# VOLTAGE_SOURCE.net
KiCad netlist of a schematic drawn in Altium Designer
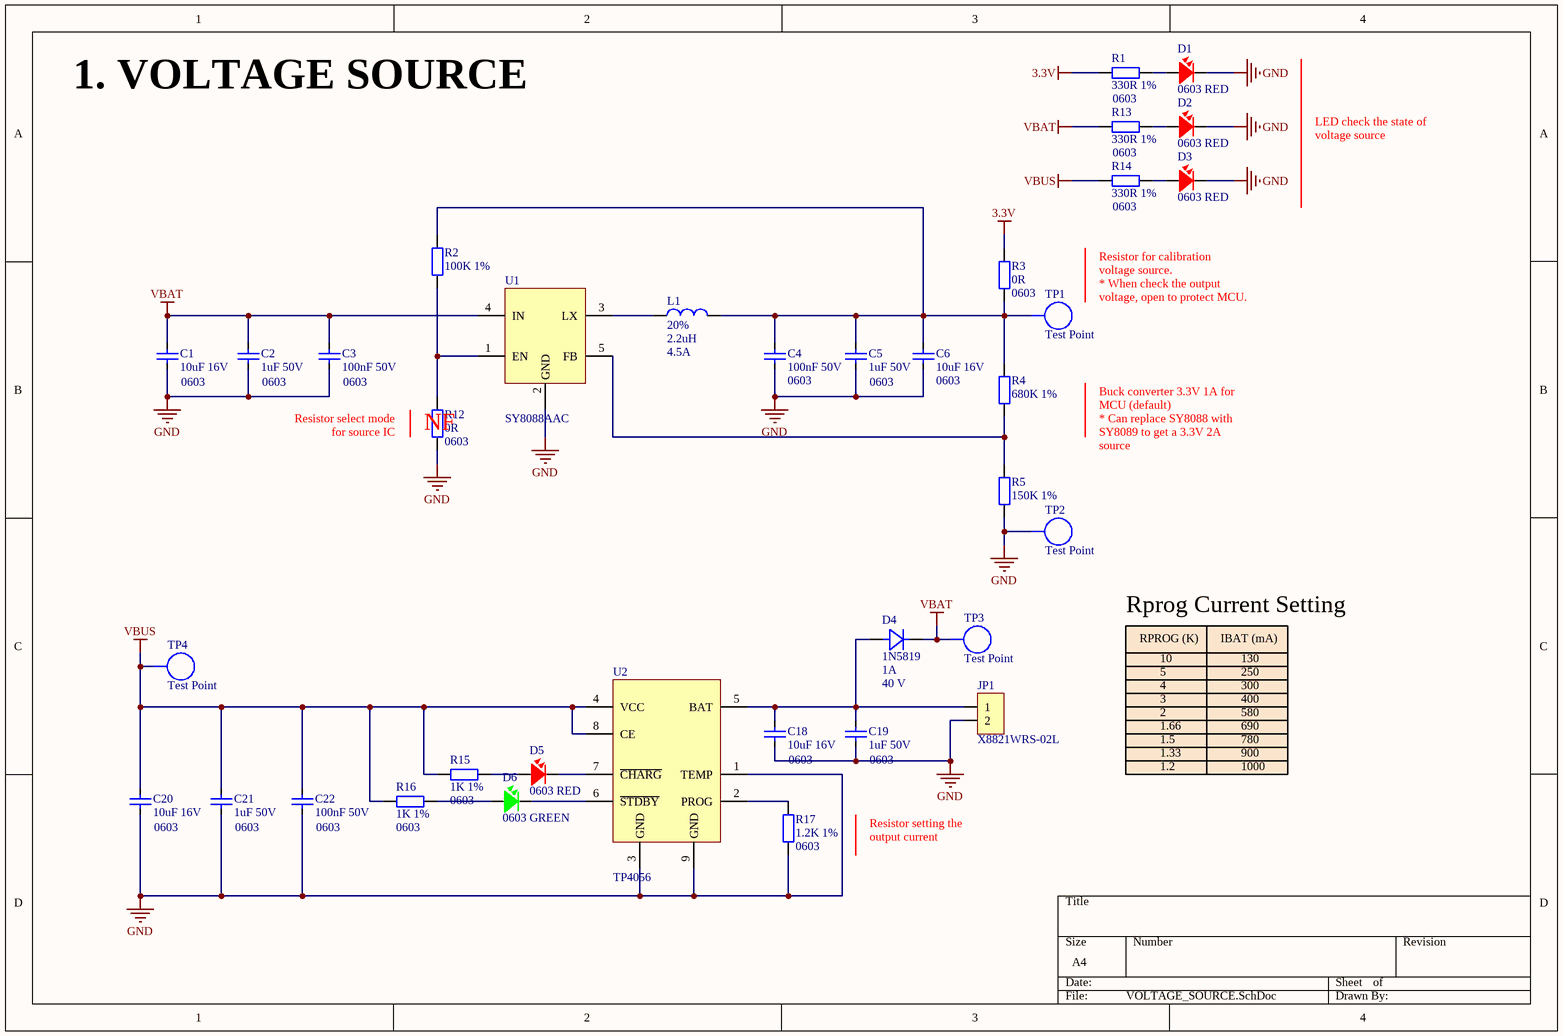
[diagram p0: VOLTAGE_SOURCE.SchDoc]

(export (version "E")
  (design (tool "Eeschema 10.0.6"))
  (components
    (comp (ref "C1")
      (value "10uF 16V")
      (footprint "CAP_SMD_0603")
      (description "10 µF ±20% 16V Ceramic Capacitor X6S 0603 (1608 Metric)")
      (fields
        (field (name "MANUFACTURER") "Murata Electronics")
        (field (name "MANUFACTURE PART NUMBER") "GRM188C81C106MA73D")
        (field (name "SIZE") "0603")
      )
      (libsource (lib "Capacitors") (part "C0603_MLCC_10uF_16V"))
    )
    (comp (ref "C2")
      (value "1uF 50V")
      (footprint "CAP_SMD_0603")
      (description "1 µF ±10% 50V Ceramic Capacitor X5R 0603 (1608 Metric)")
      (fields
        (field (name "MANUFACTURER") "Samsung Electro-Mechanics")
        (field (name "MANUFACTURE PART NUMBER") "CL10A105KB8NNNC")
        (field (name "SIZE") "0603")
      )
      (libsource (lib "Capacitors") (part "C0603_MLCC_1uF_50V"))
    )
    (comp (ref "C3")
      (value "100nF 50V")
      (footprint "CAP_SMD_0603")
      (description "0.1 µF ±10% 50V Ceramic Capacitor X7R 0603 (1608 Metric)")
      (fields
        (field (name "MANUFACTURER") "Samsung Electro-Mechanics")
        (field (name "MANUFACTURE PART NUMBER") "CL10B104KB8NNNC")
        (field (name "SIZE") "0603")
      )
      (libsource (lib "Capacitors") (part "C0603_MLCC_100nF_50V"))
    )
    (comp (ref "C4")
      (value "100nF 50V")
      (footprint "CAP_SMD_0603")
      (description "0.1 µF ±10% 50V Ceramic Capacitor X7R 0603 (1608 Metric)")
      (fields
        (field (name "MANUFACTURER") "Samsung Electro-Mechanics")
        (field (name "MANUFACTURE PART NUMBER") "CL10B104KB8NNNC")
        (field (name "SIZE") "0603")
      )
      (libsource (lib "Capacitors") (part "C0603_MLCC_100nF_50V"))
    )
    (comp (ref "C5")
      (value "1uF 50V")
      (footprint "CAP_SMD_0603")
      (description "1 µF ±10% 50V Ceramic Capacitor X5R 0603 (1608 Metric)")
      (fields
        (field (name "MANUFACTURER") "Samsung Electro-Mechanics")
        (field (name "MANUFACTURE PART NUMBER") "CL10A105KB8NNNC")
        (field (name "SIZE") "0603")
      )
      (libsource (lib "Capacitors") (part "C0603_MLCC_1uF_50V"))
    )
    (comp (ref "C6")
      (value "10uF 16V")
      (footprint "CAP_SMD_0603")
      (description "10 µF ±20% 16V Ceramic Capacitor X6S 0603 (1608 Metric)")
      (fields
        (field (name "MANUFACTURER") "Murata Electronics")
        (field (name "MANUFACTURE PART NUMBER") "GRM188C81C106MA73D")
        (field (name "SIZE") "0603")
      )
      (libsource (lib "Capacitors") (part "C0603_MLCC_10uF_16V"))
    )
    (comp (ref "C18")
      (value "10uF 16V")
      (footprint "CAP_SMD_0603")
      (description "10 µF ±20% 16V Ceramic Capacitor X6S 0603 (1608 Metric)")
      (fields
        (field (name "MANUFACTURER") "Murata Electronics")
        (field (name "MANUFACTURE PART NUMBER") "GRM188C81C106MA73D")
        (field (name "SIZE") "0603")
      )
      (libsource (lib "Capacitors") (part "C0603_MLCC_10uF_16V"))
    )
    (comp (ref "C19")
      (value "1uF 50V")
      (footprint "CAP_SMD_0603")
      (description "1 µF ±10% 50V Ceramic Capacitor X5R 0603 (1608 Metric)")
      (fields
        (field (name "MANUFACTURER") "Samsung Electro-Mechanics")
        (field (name "MANUFACTURE PART NUMBER") "CL10A105KB8NNNC")
        (field (name "SIZE") "0603")
      )
      (libsource (lib "Capacitors") (part "C0603_MLCC_1uF_50V"))
    )
    (comp (ref "C20")
      (value "10uF 16V")
      (footprint "CAP_SMD_0603")
      (description "10 µF ±20% 16V Ceramic Capacitor X6S 0603 (1608 Metric)")
      (fields
        (field (name "MANUFACTURER") "Murata Electronics")
        (field (name "MANUFACTURE PART NUMBER") "GRM188C81C106MA73D")
        (field (name "SIZE") "0603")
      )
      (libsource (lib "Capacitors") (part "C0603_MLCC_10uF_16V"))
    )
    (comp (ref "C21")
      (value "1uF 50V")
      (footprint "CAP_SMD_0603")
      (description "1 µF ±10% 50V Ceramic Capacitor X5R 0603 (1608 Metric)")
      (fields
        (field (name "MANUFACTURER") "Samsung Electro-Mechanics")
        (field (name "MANUFACTURE PART NUMBER") "CL10A105KB8NNNC")
        (field (name "SIZE") "0603")
      )
      (libsource (lib "Capacitors") (part "C0603_MLCC_1uF_50V"))
    )
    (comp (ref "C22")
      (value "100nF 50V")
      (footprint "CAP_SMD_0603")
      (description "0.1 µF ±10% 50V Ceramic Capacitor X7R 0603 (1608 Metric)")
      (fields
        (field (name "MANUFACTURER") "Samsung Electro-Mechanics")
        (field (name "MANUFACTURE PART NUMBER") "CL10B104KB8NNNC")
        (field (name "SIZE") "0603")
      )
      (libsource (lib "Capacitors") (part "C0603_MLCC_100nF_50V"))
    )
    (comp (ref "D1")
      (value "0603 RED")
      (footprint "LED-0603")
      (description "Red 625nm LED Indication - Discrete 2V 0603 (1608 Metric)")
      (fields
        (field (name "MANUFACTURER") "Würth Elektronik")
        (field (name "MANUFACTURE PART NUMBER") "150060RS75000")
      )
      (libsource (lib "LEDs") (part "LED_0603_RED"))
    )
    (comp (ref "D2")
      (value "0603 RED")
      (footprint "LED-0603")
      (description "Red 625nm LED Indication - Discrete 2V 0603 (1608 Metric)")
      (fields
        (field (name "MANUFACTURER") "Würth Elektronik")
        (field (name "MANUFACTURE PART NUMBER") "150060RS75000")
      )
      (libsource (lib "LEDs") (part "LED_0603_RED"))
    )
    (comp (ref "D3")
      (value "0603 RED")
      (footprint "LED-0603")
      (description "Red 625nm LED Indication - Discrete 2V 0603 (1608 Metric)")
      (fields
        (field (name "MANUFACTURER") "Würth Elektronik")
        (field (name "MANUFACTURE PART NUMBER") "150060RS75000")
      )
      (libsource (lib "LEDs") (part "LED_0603_RED"))
    )
    (comp (ref "D4")
      (value "1N5819")
      (footprint "DIO-SMD-123")
      (description "Diode 40 V 1A Surface Mount SOD-123")
      (fields
        (field (name "MANUFACTURER") "Diodes Incorporated")
        (field (name "MANUFACTURE PART NUMBER") "1N5819HW-7-F")
        (field (name "CURRENT - AVERAGE RECTIFIED (IO)") "1A")
        (field (name "VOLTAGE - DC REVERSE (VR) (MAX)") "40 V")
      )
      (libsource (lib "Diode") (part "1N5819"))
    )
    (comp (ref "D5")
      (value "0603 RED")
      (footprint "LED-0603")
      (description "Red 625nm LED Indication - Discrete 2V 0603 (1608 Metric)")
      (fields
        (field (name "MANUFACTURER") "Würth Elektronik")
        (field (name "MANUFACTURE PART NUMBER") "150060RS75000")
      )
      (libsource (lib "LEDs") (part "LED_0603_RED"))
    )
    (comp (ref "D6")
      (value "0603 GREEN")
      (footprint "LED-0603")
      (description "Green 520nm LED Indication - Discrete 3.2V 0603 (1608 Metric)")
      (fields
        (field (name "MANUFACTURER") "Würth Elektronik")
        (field (name "MANUFACTURE PART NUMBER") "150060GS75000")
      )
      (libsource (lib "LEDs") (part "LED_0603_GREEN"))
    )
    (comp (ref "JP1")
      (value "X8821WRS-02L")
      (footprint "CONN_X8821WRS-02L-LPSN")
      (fields
        (field (name "MANUFACTURER") "XKB Connection")
        (field (name "MANUFACTURE PART NUMBER") "X8821WRS-02L-LPSN")
      )
      (libsource (lib "Connectors") (part "X8821WRS-02L"))
    )
    (comp (ref "L1")
      (value "2.2uH 4.5A 20%")
      (footprint "L0420")
      (description "4.5A 2.2uH Molding Choke ±20% 5A SMD,0420 Power Inductors ROHS")
      (fields
        (field (name "MANUFACTURER") "XR")
        (field (name "MANUFACTURE PART NUMBER") "XR0420-2R2M")
        (field (name "TOLERANCE") "20%")
        (field (name "INDUCTOR") "2.2uH")
        (field (name "CURRENT") "4.5A")
      )
      (libsource (lib "Inductors") (part "L_0420_2.2uH_4.5A"))
    )
    (comp (ref "R1")
      (value "330R 1%")
      (footprint "RES_SMD_0603")
      (description "330 Ohms ±1% 0.1W, 1/10W Chip Resistor 0603 (1608 Metric) Thick Film")
      (fields
        (field (name "MANUFACTURER") "TE Connectivity Passive Product")
        (field (name "MANUFACTURE PART NUMBER") "CRG0603F330R")
        (field (name "SIZE") "0603")
      )
      (libsource (lib "Resistors") (part "R0603_330R"))
    )
    (comp (ref "R2")
      (value "100K 1%")
      (footprint "RES_SMD_0603")
      (description "100 kOhms ±1% 0.1W, 1/10W Chip Resistor 0603 (1608 Metric) Moisture Resistant Thick Film")
      (fields
        (field (name "MANUFACTURER") "YAGEO")
        (field (name "MANUFACTURE PART NUMBER") "RC0603FR-07100KL")
      )
      (libsource (lib "Resistors") (part "R0603_100K"))
    )
    (comp (ref "R3")
      (value "0R")
      (footprint "RES_SMD_0603")
      (description "0 Ohms Jumper Chip Resistor 0603 (1608 Metric) Automotive AEC-Q200 Thick Film")
      (fields
        (field (name "MANUFACTURER") "Stackpole Electronics Inc")
        (field (name "MANUFACTURE PART NUMBER") "RMCF0603ZT0R00")
        (field (name "SIZE") "0603")
      )
      (libsource (lib "Resistors") (part "R0603_0R"))
    )
    (comp (ref "R4")
      (value "680K 1%")
      (footprint "RES_SMD_0603")
      (description "680 kOhms ±1% 0.1W, 1/10W Chip Resistor 0603 (1608 Metric) Moisture Resistant Thick Film")
      (fields
        (field (name "MANUFACTURER") "YAGEO")
        (field (name "MANUFACTURE PART NUMBER") "RC0603FR-07680KL")
      )
      (libsource (lib "Resistors") (part "R0603_680K"))
    )
    (comp (ref "R5")
      (value "150K 1%")
      (footprint "RES_SMD_0603")
      (description "150 kOhms ±1% 0.1W, 1/10W Chip Resistor 0603 (1608 Metric) Automotive AEC-Q200 Thick Film")
      (fields
        (field (name "MANUFACTURER") "Vishay Dale")
        (field (name "MANUFACTURE PART NUMBER") "CRCW0603150KFKEA")
      )
      (libsource (lib "Resistors") (part "R0603_150K"))
    )
    (comp (ref "R12")
      (value "0R")
      (footprint "RES_SMD_0603")
      (description "0 Ohms Jumper Chip Resistor 0603 (1608 Metric) Automotive AEC-Q200 Thick Film")
      (fields
        (field (name "MANUFACTURER") "Stackpole Electronics Inc")
        (field (name "MANUFACTURE PART NUMBER") "RMCF0603ZT0R00")
        (field (name "SIZE") "0603")
      )
      (libsource (lib "Resistors") (part "R0603_0R"))
    )
    (comp (ref "R13")
      (value "330R 1%")
      (footprint "RES_SMD_0603")
      (description "330 Ohms ±1% 0.1W, 1/10W Chip Resistor 0603 (1608 Metric) Thick Film")
      (fields
        (field (name "MANUFACTURER") "TE Connectivity Passive Product")
        (field (name "MANUFACTURE PART NUMBER") "CRG0603F330R")
        (field (name "SIZE") "0603")
      )
      (libsource (lib "Resistors") (part "R0603_330R"))
    )
    (comp (ref "R14")
      (value "330R 1%")
      (footprint "RES_SMD_0603")
      (description "330 Ohms ±1% 0.1W, 1/10W Chip Resistor 0603 (1608 Metric) Thick Film")
      (fields
        (field (name "MANUFACTURER") "TE Connectivity Passive Product")
        (field (name "MANUFACTURE PART NUMBER") "CRG0603F330R")
        (field (name "SIZE") "0603")
      )
      (libsource (lib "Resistors") (part "R0603_330R"))
    )
    (comp (ref "R15")
      (value "1K 1%")
      (footprint "RES_SMD_0603")
      (description "1 kOhms ±1% 0.1W, 1/10W Chip Resistor 0603 (1608 Metric) Moisture Resistant Thick Film")
      (fields
        (field (name "MANUFACTURER") "YAGEO")
        (field (name "MANUFACTURE PART NUMBER") "RC0603FR-071KL")
        (field (name "SIZE") "0603")
      )
      (libsource (lib "Resistors") (part "R0603_1K"))
    )
    (comp (ref "R16")
      (value "1K 1%")
      (footprint "RES_SMD_0603")
      (description "1 kOhms ±1% 0.1W, 1/10W Chip Resistor 0603 (1608 Metric) Moisture Resistant Thick Film")
      (fields
        (field (name "MANUFACTURER") "YAGEO")
        (field (name "MANUFACTURE PART NUMBER") "RC0603FR-071KL")
        (field (name "SIZE") "0603")
      )
      (libsource (lib "Resistors") (part "R0603_1K"))
    )
    (comp (ref "R17")
      (value "1.2K 1%")
      (footprint "RES_SMD_0603")
      (description "1.2 kOhms ±1% 0.1W, 1/10W Chip Resistor 0603 (1608 Metric) Automotive AEC-Q200 Thick Film")
      (fields
        (field (name "MANUFACTURER") "Stackpole Electronics Inc")
        (field (name "MANUFACTURE PART NUMBER") "RC0603FR-071KL")
        (field (name "SIZE") "0603")
      )
      (libsource (lib "Resistors") (part "R0603_1.2K"))
    )
    (comp (ref "TP1")
      (value "Test Point")
      (footprint "TEST_POINT")
      (libsource (lib "Connectors") (part "TEST_POINT"))
    )
    (comp (ref "TP2")
      (value "Test Point")
      (footprint "TEST_POINT")
      (libsource (lib "Connectors") (part "TEST_POINT"))
    )
    (comp (ref "TP3")
      (value "Test Point")
      (footprint "TEST_POINT")
      (libsource (lib "Connectors") (part "TEST_POINT"))
    )
    (comp (ref "TP4")
      (value "Test Point")
      (footprint "TEST_POINT")
      (libsource (lib "Connectors") (part "TEST_POINT"))
    )
    (comp (ref "U1")
      (value "SY8088AAC")
      (footprint "SOT23_5")
      (description "Step-down type SOT-23-5 DC-DC Converters ROHS")
      (fields (field (name "MANUFACTURER") "Silergy Corp"))
      (libsource (lib "Voltage_Regulators") (part "SY8088AAC"))
    )
    (comp (ref "U2")
      (value "TP4056")
      (footprint "ESOP-8")
      (description "ESOP-8 Battery Management ICs ROHS")
      (fields (field (name "MANUFACTURER") "UMW(Youtai Semiconductor Co., Ltd.)"))
      (libsource (lib "ICs") (part "TP4056"))
    )
  )
  (nets
    (net (code "1") (name "3.3V") (class "Default")
      (node (ref "R1") (pin "1") (pinfunction "1_1") (pintype "passive"))
      (node (ref "R3") (pin "2") (pinfunction "2_2") (pintype "passive"))
    )
    (net (code "2") (name "GND") (class "Default")
      (node (ref "C1") (pin "1") (pinfunction "1_1") (pintype "passive"))
      (node (ref "C18") (pin "1") (pinfunction "1_1") (pintype "passive"))
      (node (ref "C19") (pin "1") (pinfunction "1_1") (pintype "passive"))
      (node (ref "C2") (pin "1") (pinfunction "1_1") (pintype "passive"))
      (node (ref "C20") (pin "1") (pinfunction "1_1") (pintype "passive"))
      (node (ref "C21") (pin "1") (pinfunction "1_1") (pintype "passive"))
      (node (ref "C22") (pin "1") (pinfunction "1_1") (pintype "passive"))
      (node (ref "C3") (pin "1") (pinfunction "1_1") (pintype "passive"))
      (node (ref "C4") (pin "1") (pinfunction "1_1") (pintype "passive"))
      (node (ref "C5") (pin "1") (pinfunction "1_1") (pintype "passive"))
      (node (ref "C6") (pin "1") (pinfunction "1_1") (pintype "passive"))
      (node (ref "D1") (pin "2") (pinfunction "2_2") (pintype "passive"))
      (node (ref "D2") (pin "2") (pinfunction "2_2") (pintype "passive"))
      (node (ref "D3") (pin "2") (pinfunction "2_2") (pintype "passive"))
      (node (ref "JP1") (pin "2") (pinfunction "2_2") (pintype "passive"))
      (node (ref "R12") (pin "1") (pinfunction "1_1") (pintype "passive"))
      (node (ref "R17") (pin "1") (pinfunction "1_1") (pintype "passive"))
      (node (ref "R5") (pin "1") (pinfunction "1_1") (pintype "passive"))
      (node (ref "TP2") (pin "1") (pinfunction "1_1") (pintype "passive"))
      (node (ref "U1") (pin "2") (pinfunction "GND_2") (pintype "passive"))
      (node (ref "U2") (pin "1") (pinfunction "TEMP_1") (pintype "passive"))
      (node (ref "U2") (pin "3") (pinfunction "GND_3") (pintype "passive"))
      (node (ref "U2") (pin "9") (pinfunction "GND_9") (pintype "passive"))
    )
    (net (code "3") (name "Net-(C4-Pad2)") (class "Default")
      (node (ref "C4") (pin "2") (pinfunction "2_2") (pintype "passive"))
      (node (ref "C5") (pin "2") (pinfunction "2_2") (pintype "passive"))
      (node (ref "C6") (pin "2") (pinfunction "2_2") (pintype "passive"))
      (node (ref "L1") (pin "2") (pinfunction "2_2") (pintype "passive"))
      (node (ref "R2") (pin "2") (pinfunction "2_2") (pintype "passive"))
      (node (ref "R3") (pin "1") (pinfunction "1_1") (pintype "passive"))
      (node (ref "R4") (pin "2") (pinfunction "2_2") (pintype "passive"))
      (node (ref "TP1") (pin "1") (pinfunction "1_1") (pintype "passive"))
    )
    (net (code "4") (name "Net-(D1-Pad1)") (class "Default")
      (node (ref "D1") (pin "1") (pinfunction "1_1") (pintype "passive"))
      (node (ref "R1") (pin "2") (pinfunction "2_2") (pintype "passive"))
    )
    (net (code "5") (name "Net-(D2-Pad1)") (class "Default")
      (node (ref "D2") (pin "1") (pinfunction "1_1") (pintype "passive"))
      (node (ref "R13") (pin "2") (pinfunction "2_2") (pintype "passive"))
    )
    (net (code "6") (name "Net-(D3-Pad1)") (class "Default")
      (node (ref "D3") (pin "1") (pinfunction "1_1") (pintype "passive"))
      (node (ref "R14") (pin "2") (pinfunction "2_2") (pintype "passive"))
    )
    (net (code "7") (name "Net-(D5-Pad1)") (class "Default")
      (node (ref "D5") (pin "1") (pinfunction "1_1") (pintype "passive"))
      (node (ref "R15") (pin "1") (pinfunction "1_1") (pintype "passive"))
    )
    (net (code "8") (name "Net-(D6-Pad1)") (class "Default")
      (node (ref "D6") (pin "1") (pinfunction "1_1") (pintype "passive"))
      (node (ref "R16") (pin "1") (pinfunction "1_1") (pintype "passive"))
    )
    (net (code "9") (name "Net-(U1-EN)") (class "Default")
      (node (ref "R12") (pin "2") (pinfunction "2_2") (pintype "passive"))
      (node (ref "R2") (pin "1") (pinfunction "1_1") (pintype "passive"))
      (node (ref "U1") (pin "1") (pinfunction "EN_1") (pintype "passive"))
    )
    (net (code "10") (name "Net-(U1-FB)") (class "Default")
      (node (ref "R4") (pin "1") (pinfunction "1_1") (pintype "passive"))
      (node (ref "R5") (pin "2") (pinfunction "2_2") (pintype "passive"))
      (node (ref "U1") (pin "5") (pinfunction "FB_5") (pintype "passive"))
    )
    (net (code "11") (name "Net-(U1-LX)") (class "Default")
      (node (ref "L1") (pin "1") (pinfunction "1_1") (pintype "passive"))
      (node (ref "U1") (pin "3") (pinfunction "LX_3") (pintype "passive"))
    )
    (net (code "12") (name "Net-(U2-BAT)") (class "Default")
      (node (ref "C18") (pin "2") (pinfunction "2_2") (pintype "passive"))
      (node (ref "C19") (pin "2") (pinfunction "2_2") (pintype "passive"))
      (node (ref "D4") (pin "A") (pinfunction "A_A") (pintype "passive"))
      (node (ref "JP1") (pin "1") (pinfunction "1_1") (pintype "passive"))
      (node (ref "U2") (pin "5") (pinfunction "BAT_5") (pintype "passive"))
    )
    (net (code "13") (name "Net-(U2-PROG)") (class "Default")
      (node (ref "R17") (pin "2") (pinfunction "2_2") (pintype "passive"))
      (node (ref "U2") (pin "2") (pinfunction "PROG_2") (pintype "passive"))
    )
    (net (code "14") (name "Net-(U2-~{CHARG})") (class "Default")
      (node (ref "D5") (pin "2") (pinfunction "2_2") (pintype "passive"))
      (node (ref "U2") (pin "7") (pinfunction "~{CHARG}_7") (pintype "passive"))
    )
    (net (code "15") (name "Net-(U2-~{STDBY})") (class "Default")
      (node (ref "D6") (pin "2") (pinfunction "2_2") (pintype "passive"))
      (node (ref "U2") (pin "6") (pinfunction "~{STDBY}_6") (pintype "passive"))
    )
    (net (code "16") (name "VBAT") (class "Default")
      (node (ref "C1") (pin "2") (pinfunction "2_2") (pintype "passive"))
      (node (ref "C2") (pin "2") (pinfunction "2_2") (pintype "passive"))
      (node (ref "C3") (pin "2") (pinfunction "2_2") (pintype "passive"))
      (node (ref "D4") (pin "C") (pinfunction "C_C") (pintype "passive"))
      (node (ref "R13") (pin "1") (pinfunction "1_1") (pintype "passive"))
      (node (ref "TP3") (pin "1") (pinfunction "1_1") (pintype "passive"))
      (node (ref "U1") (pin "4") (pinfunction "IN_4") (pintype "passive"))
    )
    (net (code "17") (name "VBUS") (class "Default")
      (node (ref "C20") (pin "2") (pinfunction "2_2") (pintype "passive"))
      (node (ref "C21") (pin "2") (pinfunction "2_2") (pintype "passive"))
      (node (ref "C22") (pin "2") (pinfunction "2_2") (pintype "passive"))
      (node (ref "R14") (pin "1") (pinfunction "1_1") (pintype "passive"))
      (node (ref "R15") (pin "2") (pinfunction "2_2") (pintype "passive"))
      (node (ref "R16") (pin "2") (pinfunction "2_2") (pintype "passive"))
      (node (ref "TP4") (pin "1") (pinfunction "1_1") (pintype "passive"))
      (node (ref "U2") (pin "4") (pinfunction "VCC_4") (pintype "passive"))
      (node (ref "U2") (pin "8") (pinfunction "CE_8") (pintype "passive"))
    )
  )
)
